# lithium_battery_manager_v12.net
KiCad netlist of a schematic drawn in EAGLE
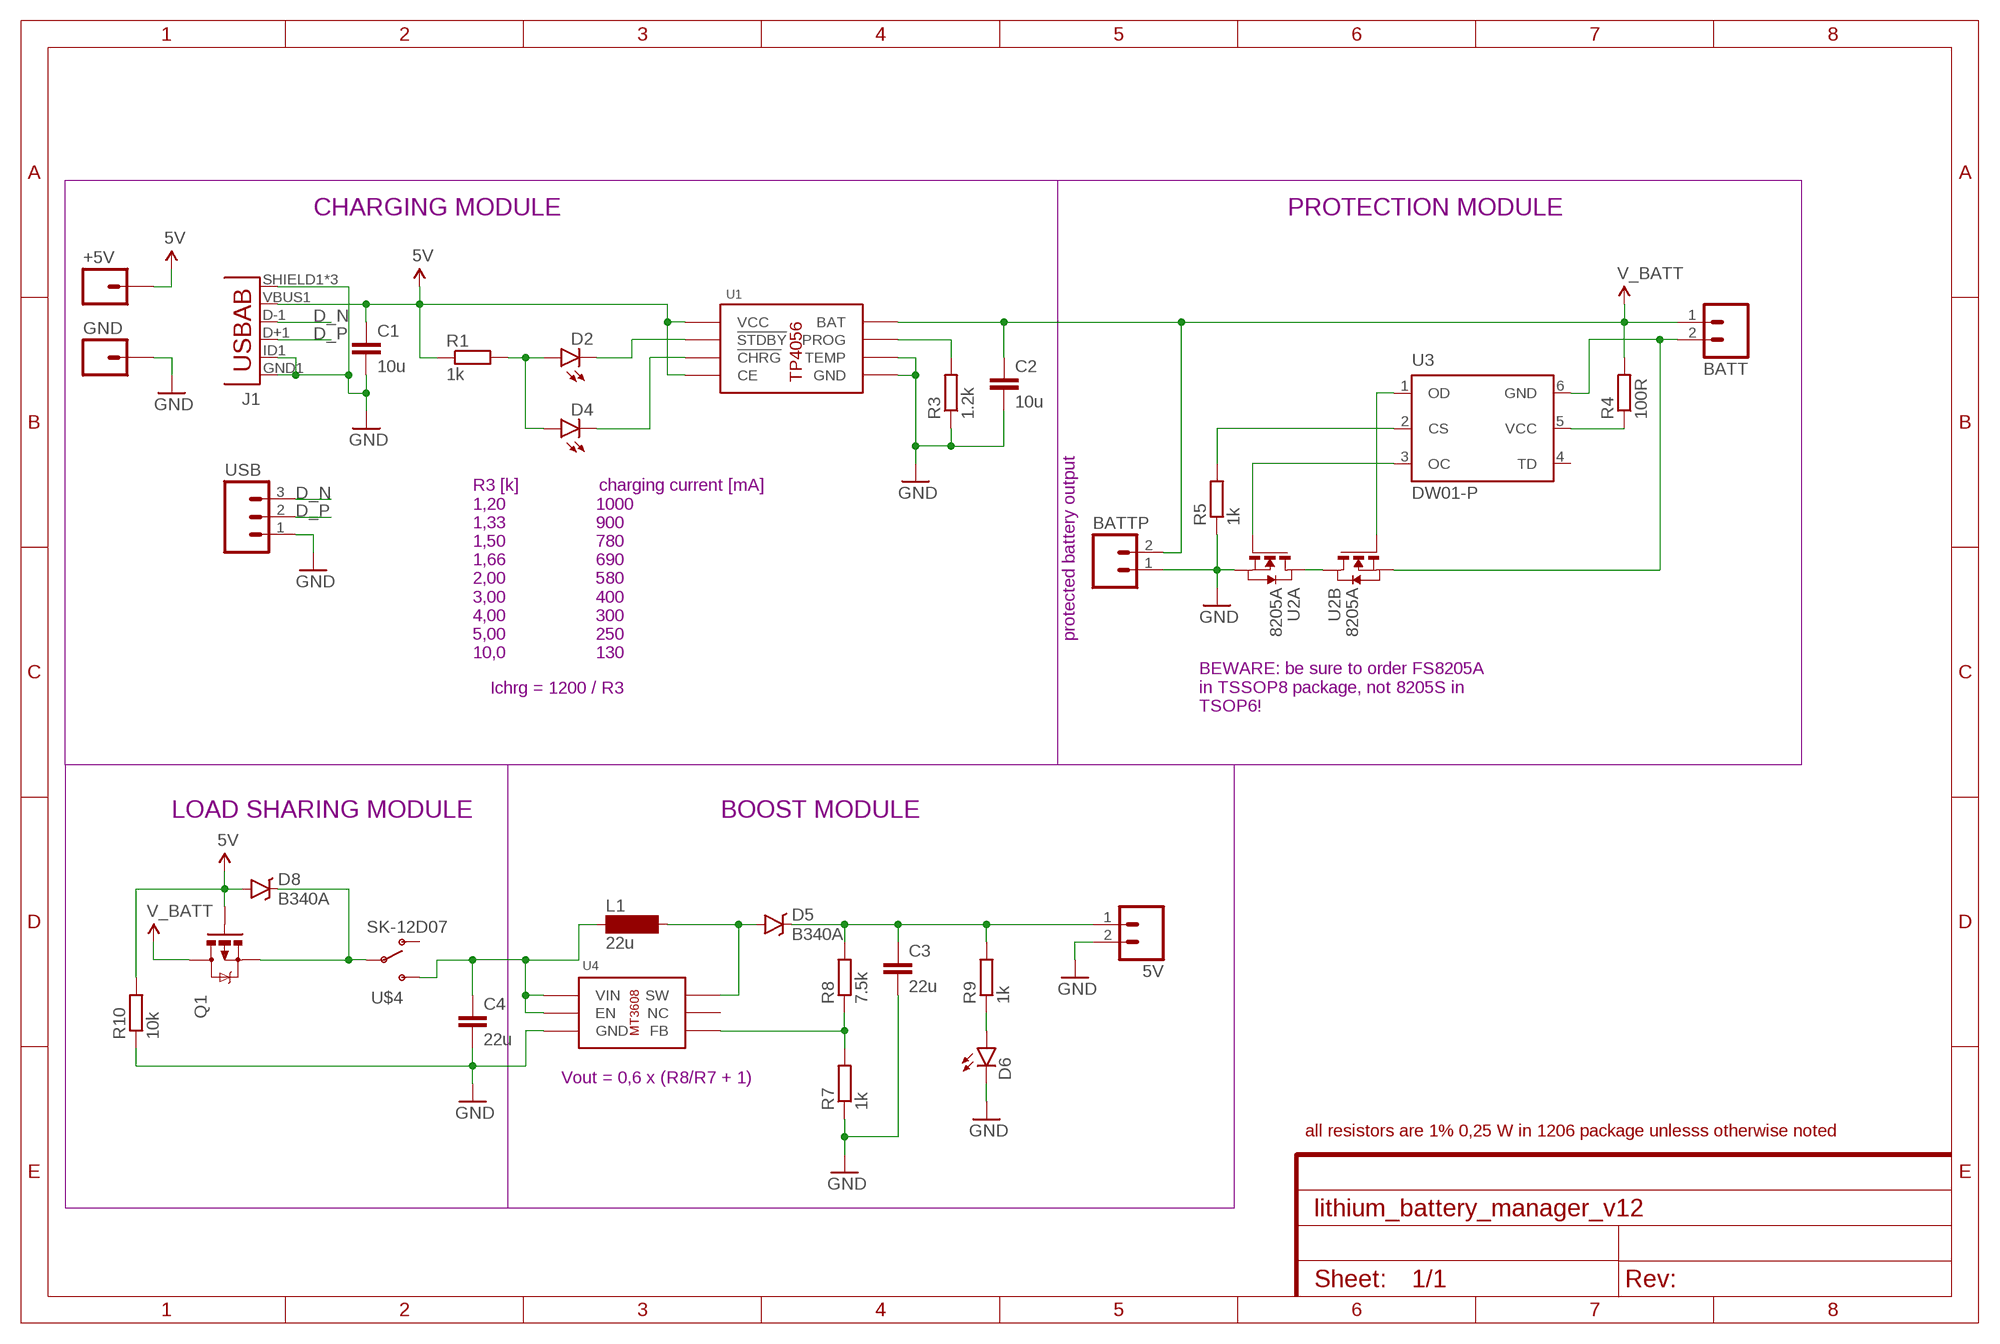
[diagram p0: schematic, sheet 1]

(export (version "E")
  (design (tool "Eeschema 10.0.6"))
  (components
    (comp (ref "+5V")
      (value "M01OFFSET")
      (footprint "eagle-import:1X01_OFFSET")
      (libsource (lib "eagle-import") (part "M01OFFSET"))
    )
    (comp (ref "5V")
      (value "M02PTH3")
      (footprint "eagle-import:1X02_LONGPADS")
      (libsource (lib "eagle-import") (part "M02PTH3"))
    )
    (comp (ref "BATT")
      (value "M02PTH3")
      (footprint "eagle-import:1X02_LONGPADS")
      (libsource (lib "eagle-import") (part "M02PTH3"))
    )
    (comp (ref "BATTP")
      (value "M02PTH3")
      (footprint "eagle-import:1X02_LONGPADS")
      (libsource (lib "eagle-import") (part "M02PTH3"))
    )
    (comp (ref "C1")
      (value "10u")
      (footprint "eagle-import:C1206")
      (libsource (lib "eagle-import") (part "C-EUC1206"))
    )
    (comp (ref "C2")
      (value "10u")
      (footprint "eagle-import:C1206")
      (libsource (lib "eagle-import") (part "C-EUC1206"))
    )
    (comp (ref "C3")
      (value "22u")
      (footprint "eagle-import:C1206")
      (libsource (lib "eagle-import") (part "C-EUC1206"))
    )
    (comp (ref "C4")
      (value "22u")
      (footprint "eagle-import:C1206")
      (libsource (lib "eagle-import") (part "C-EUC1206"))
    )
    (comp (ref "D2")
      (value "LED-CONN")
      (footprint "eagle-import:LED5MM")
      (libsource (lib "eagle-import") (part "LED-CONN"))
    )
    (comp (ref "D4")
      (value "LED-CONN")
      (footprint "eagle-import:LED5MM")
      (libsource (lib "eagle-import") (part "LED-CONN"))
    )
    (comp (ref "D5")
      (value "B340A")
      (footprint "eagle-import:SMA-DIODE")
      (libsource (lib "eagle-import") (part "DIODE-SCHOTTKY-B340A"))
    )
    (comp (ref "D6")
      (value "LED-CONN")
      (footprint "eagle-import:LED5MM")
      (libsource (lib "eagle-import") (part "LED-CONN"))
    )
    (comp (ref "D8")
      (value "B340A")
      (footprint "eagle-import:SMA-DIODE")
      (libsource (lib "eagle-import") (part "DIODE-SCHOTTKY-B340A"))
    )
    (comp (ref "GND")
      (value "M01OFFSET")
      (footprint "eagle-import:1X01_OFFSET")
      (libsource (lib "eagle-import") (part "M01OFFSET"))
    )
    (comp (ref "J1")
      (value "USB-ABCONN-11794")
      (footprint "eagle-import:USB-AB-MICRO-SMD_V03")
      (libsource (lib "eagle-import") (part "USB-ABCONN-11794"))
    )
    (comp (ref "L1")
      (value "22u")
      (footprint "eagle-import:MS85")
      (libsource (lib "eagle-import") (part "MS85"))
    )
    (comp (ref "Q1")
      (value "MOSFET-PCHANNEL")
      (footprint "eagle-import:SOT23-3")
      (libsource (lib "eagle-import") (part "MOSFET-PCHANNEL"))
    )
    (comp (ref "R1")
      (value "1k")
      (footprint "eagle-import:R1206")
      (libsource (lib "eagle-import") (part "R-EU_R1206"))
    )
    (comp (ref "R3")
      (value "1.2k")
      (footprint "eagle-import:R1206")
      (libsource (lib "eagle-import") (part "R-EU_R1206"))
    )
    (comp (ref "R4")
      (value "100R")
      (footprint "eagle-import:R1206")
      (libsource (lib "eagle-import") (part "R-EU_R1206"))
    )
    (comp (ref "R5")
      (value "1k")
      (footprint "eagle-import:R1206")
      (libsource (lib "eagle-import") (part "R-EU_R1206"))
    )
    (comp (ref "R7")
      (value "1k")
      (footprint "eagle-import:R1206")
      (libsource (lib "eagle-import") (part "R-EU_R1206"))
    )
    (comp (ref "R8")
      (value "7.5k")
      (footprint "eagle-import:R1206")
      (libsource (lib "eagle-import") (part "R-EU_R1206"))
    )
    (comp (ref "R9")
      (value "1k")
      (footprint "eagle-import:R1206")
      (libsource (lib "eagle-import") (part "R-EU_R1206"))
    )
    (comp (ref "R10")
      (value "10k")
      (footprint "eagle-import:R1206")
      (libsource (lib "eagle-import") (part "R-EU_R1206"))
    )
    (comp (ref "U$4")
      (value "SK-12D07")
      (footprint "eagle-import:SK12SWITCH")
      (libsource (lib "eagle-import") (part "SK-12D07"))
    )
    (comp (ref "U1")
      (value "TP4056")
      (footprint "eagle-import:SOP8")
      (libsource (lib "eagle-import") (part "TP4056"))
    )
    (comp (ref "U2")
      (value "8205A")
      (footprint "eagle-import:TSSOP8")
      (libsource (lib "eagle-import") (part "8205A"))
    )
    (comp (ref "U3")
      (value "DW01-P")
      (footprint "eagle-import:SOT23-6L")
      (libsource (lib "eagle-import") (part "DW01-P"))
    )
    (comp (ref "U4")
      (value "MT3608")
      (footprint "eagle-import:SOT23-6")
      (libsource (lib "eagle-import") (part "MT3608"))
    )
    (comp (ref "USB")
      (value "M03PTH")
      (footprint "eagle-import:1X03")
      (libsource (lib "eagle-import") (part "M03PTH"))
    )
  )
  (nets
    (net (code "1") (name "/D_N") (class "Default")
      (node (ref "J1") (pin "D-1") (pinfunction "D-_D-1") (pintype "bidirectional"))
      (node (ref "USB") (pin "3") (pinfunction "3_3") (pintype "passive"))
    )
    (net (code "2") (name "/D_P") (class "Default")
      (node (ref "J1") (pin "D+1") (pinfunction "D+_D+1") (pintype "bidirectional"))
      (node (ref "USB") (pin "2") (pinfunction "2_2") (pintype "passive"))
    )
    (net (code "3") (name "5V") (class "Default")
      (node (ref "+5V") (pin "1") (pinfunction "1_1") (pintype "passive"))
      (node (ref "C1") (pin "1") (pinfunction "1_1") (pintype "passive"))
      (node (ref "D8") (pin "A") (pinfunction "A_A") (pintype "passive"))
      (node (ref "J1") (pin "VBUS1") (pinfunction "VBUS_VBUS1") (pintype "bidirectional"))
      (node (ref "Q1") (pin "1") (pinfunction "G_1") (pintype "passive"))
      (node (ref "R1") (pin "1") (pinfunction "1_1") (pintype "passive"))
      (node (ref "R10") (pin "2") (pinfunction "2_2") (pintype "passive"))
      (node (ref "U1") (pin "4") (pinfunction "VCC_4") (pintype "bidirectional"))
      (node (ref "U1") (pin "8") (pinfunction "CE_8") (pintype "bidirectional"))
    )
    (net (code "4") (name "GND") (class "Default")
      (node (ref "5V") (pin "2") (pinfunction "2_2") (pintype "passive"))
      (node (ref "BATTP") (pin "1") (pinfunction "1_1") (pintype "passive"))
      (node (ref "C1") (pin "2") (pinfunction "2_2") (pintype "passive"))
      (node (ref "C2") (pin "2") (pinfunction "2_2") (pintype "passive"))
      (node (ref "C3") (pin "2") (pinfunction "2_2") (pintype "passive"))
      (node (ref "C4") (pin "2") (pinfunction "2_2") (pintype "passive"))
      (node (ref "D6") (pin "K") (pinfunction "C_K") (pintype "passive"))
      (node (ref "GND") (pin "1") (pinfunction "1_1") (pintype "passive"))
      (node (ref "J1") (pin "GND1") (pinfunction "GND_GND1") (pintype "bidirectional"))
      (node (ref "J1") (pin "ID1") (pinfunction "USBID_ID1") (pintype "bidirectional"))
      (node (ref "J1") (pin "SHIELD1") (pinfunction "SHIELD_SHIELD1") (pintype "bidirectional"))
      (node (ref "J1") (pin "SHIELD2") (pinfunction "SHIELD_SHIELD2") (pintype "bidirectional"))
      (node (ref "J1") (pin "SHIELD3") (pinfunction "SHIELD_SHIELD3") (pintype "bidirectional"))
      (node (ref "R10") (pin "1") (pinfunction "1_1") (pintype "passive"))
      (node (ref "R3") (pin "1") (pinfunction "1_1") (pintype "passive"))
      (node (ref "R5") (pin "1") (pinfunction "1_1") (pintype "passive"))
      (node (ref "R7") (pin "1") (pinfunction "1_1") (pintype "passive"))
      (node (ref "U1") (pin "1") (pinfunction "TEMP_1") (pintype "bidirectional"))
      (node (ref "U1") (pin "3") (pinfunction "GND_3") (pintype "bidirectional"))
      (node (ref "U2") (pin "2") (pinfunction "S_2") (pintype "passive"))
      (node (ref "U2") (pin "3") (pinfunction "S_3") (pintype "passive"))
      (node (ref "U4") (pin "2") (pinfunction "GND_2") (pintype "bidirectional"))
      (node (ref "USB") (pin "1") (pinfunction "1_1") (pintype "passive"))
    )
    (net (code "5") (name "Net-(5V-Pad1)") (class "Default")
      (node (ref "5V") (pin "1") (pinfunction "1_1") (pintype "passive"))
      (node (ref "C3") (pin "1") (pinfunction "1_1") (pintype "passive"))
      (node (ref "D5") (pin "C") (pinfunction "C_C") (pintype "passive"))
      (node (ref "R8") (pin "2") (pinfunction "2_2") (pintype "passive"))
      (node (ref "R9") (pin "2") (pinfunction "2_2") (pintype "passive"))
    )
    (net (code "6") (name "Net-(D2-C)") (class "Default")
      (node (ref "D2") (pin "K") (pinfunction "C_K") (pintype "passive"))
      (node (ref "U1") (pin "6") (pinfunction "~{STDBY}_6") (pintype "bidirectional"))
    )
    (net (code "7") (name "Net-(D2-PadA)") (class "Default")
      (node (ref "D2") (pin "A") (pinfunction "A_A") (pintype "passive"))
      (node (ref "D4") (pin "A") (pinfunction "A_A") (pintype "passive"))
      (node (ref "R1") (pin "2") (pinfunction "2_2") (pintype "passive"))
    )
    (net (code "8") (name "Net-(D4-C)") (class "Default")
      (node (ref "D4") (pin "K") (pinfunction "C_K") (pintype "passive"))
      (node (ref "U1") (pin "7") (pinfunction "~{CHRG}_7") (pintype "bidirectional"))
    )
    (net (code "9") (name "Net-(D6-PadA)") (class "Default")
      (node (ref "D6") (pin "A") (pinfunction "A_A") (pintype "passive"))
      (node (ref "R9") (pin "1") (pinfunction "1_1") (pintype "passive"))
    )
    (net (code "10") (name "Net-(Q1-S)") (class "Default")
      (node (ref "D8") (pin "C") (pinfunction "C_C") (pintype "passive"))
      (node (ref "Q1") (pin "2") (pinfunction "S_2") (pintype "passive"))
      (node (ref "U$4") (pin "P2") (pinfunction "P_P2") (pintype "passive"))
    )
    (net (code "11") (name "Net-(U$4-S)") (class "Default")
      (node (ref "C4") (pin "1") (pinfunction "1_1") (pintype "passive"))
      (node (ref "L1") (pin "1") (pinfunction "1_1") (pintype "passive"))
      (node (ref "U$4") (pin "IN") (pinfunction "S_IN") (pintype "passive"))
      (node (ref "U4") (pin "4") (pinfunction "EN_4") (pintype "bidirectional"))
      (node (ref "U4") (pin "5") (pinfunction "VIN_5") (pintype "bidirectional"))
    )
    (net (code "12") (name "Net-(U1-PROG)") (class "Default")
      (node (ref "R3") (pin "2") (pinfunction "2_2") (pintype "passive"))
      (node (ref "U1") (pin "2") (pinfunction "PROG_2") (pintype "bidirectional"))
    )
    (net (code "13") (name "Net-(U2A-D)") (class "Default")
      (node (ref "U2") (pin "1") (pinfunction "D_1") (pintype "passive"))
      (node (ref "U2") (pin "8") (pinfunction "D_8") (pintype "passive"))
    )
    (net (code "14") (name "Net-(U2A-G)") (class "Default")
      (node (ref "U2") (pin "4") (pinfunction "G_4") (pintype "passive"))
      (node (ref "U3") (pin "3") (pinfunction "OC_3") (pintype "power_in"))
    )
    (net (code "15") (name "Net-(U2B-G)") (class "Default")
      (node (ref "U2") (pin "5") (pinfunction "G_5") (pintype "passive"))
      (node (ref "U3") (pin "1") (pinfunction "OD_1") (pintype "power_in"))
    )
    (net (code "16") (name "Net-(U3-CS)") (class "Default")
      (node (ref "R5") (pin "2") (pinfunction "2_2") (pintype "passive"))
      (node (ref "U3") (pin "2") (pinfunction "CS_2") (pintype "input"))
    )
    (net (code "17") (name "Net-(U3-GND)") (class "Default")
      (node (ref "BATT") (pin "2") (pinfunction "2_2") (pintype "passive"))
      (node (ref "U2") (pin "6") (pinfunction "S_6") (pintype "passive"))
      (node (ref "U2") (pin "7") (pinfunction "S_7") (pintype "passive"))
      (node (ref "U3") (pin "6") (pinfunction "GND_6") (pintype "output"))
    )
    (net (code "18") (name "Net-(U3-VCC)") (class "Default")
      (node (ref "R4") (pin "1") (pinfunction "1_1") (pintype "passive"))
      (node (ref "U3") (pin "5") (pinfunction "VCC_5") (pintype "input"))
    )
    (net (code "19") (name "Net-(U4-FB)") (class "Default")
      (node (ref "R7") (pin "2") (pinfunction "2_2") (pintype "passive"))
      (node (ref "R8") (pin "1") (pinfunction "1_1") (pintype "passive"))
      (node (ref "U4") (pin "3") (pinfunction "FB_3") (pintype "bidirectional"))
    )
    (net (code "20") (name "Net-(U4-SW)") (class "Default")
      (node (ref "D5") (pin "A") (pinfunction "A_A") (pintype "passive"))
      (node (ref "L1") (pin "2") (pinfunction "2_2") (pintype "passive"))
      (node (ref "U4") (pin "1") (pinfunction "SW_1") (pintype "bidirectional"))
    )
    (net (code "21") (name "V_BATT") (class "Default")
      (node (ref "BATT") (pin "1") (pinfunction "1_1") (pintype "passive"))
      (node (ref "BATTP") (pin "2") (pinfunction "2_2") (pintype "passive"))
      (node (ref "C2") (pin "1") (pinfunction "1_1") (pintype "passive"))
      (node (ref "Q1") (pin "3") (pinfunction "D_3") (pintype "passive"))
      (node (ref "R4") (pin "2") (pinfunction "2_2") (pintype "passive"))
      (node (ref "U1") (pin "5") (pinfunction "BAT_5") (pintype "bidirectional"))
    )
    (net (code "22") (name "unconnected-(U$4-O-PadP1)") (class "Default")
      (node (ref "U$4") (pin "P1") (pinfunction "O_P1") (pintype "passive"))
    )
    (net (code "23") (name "unconnected-(U3-TD-Pad4)") (class "Default")
      (node (ref "U3") (pin "4") (pinfunction "TD_4") (pintype "output"))
    )
    (net (code "24") (name "unconnected-(U4-NC-Pad6)") (class "Default")
      (node (ref "U4") (pin "6") (pinfunction "NC_6") (pintype "bidirectional"))
    )
  )
)
